# schematic.net
KiCad netlist of a schematic drawn in EasyEDA
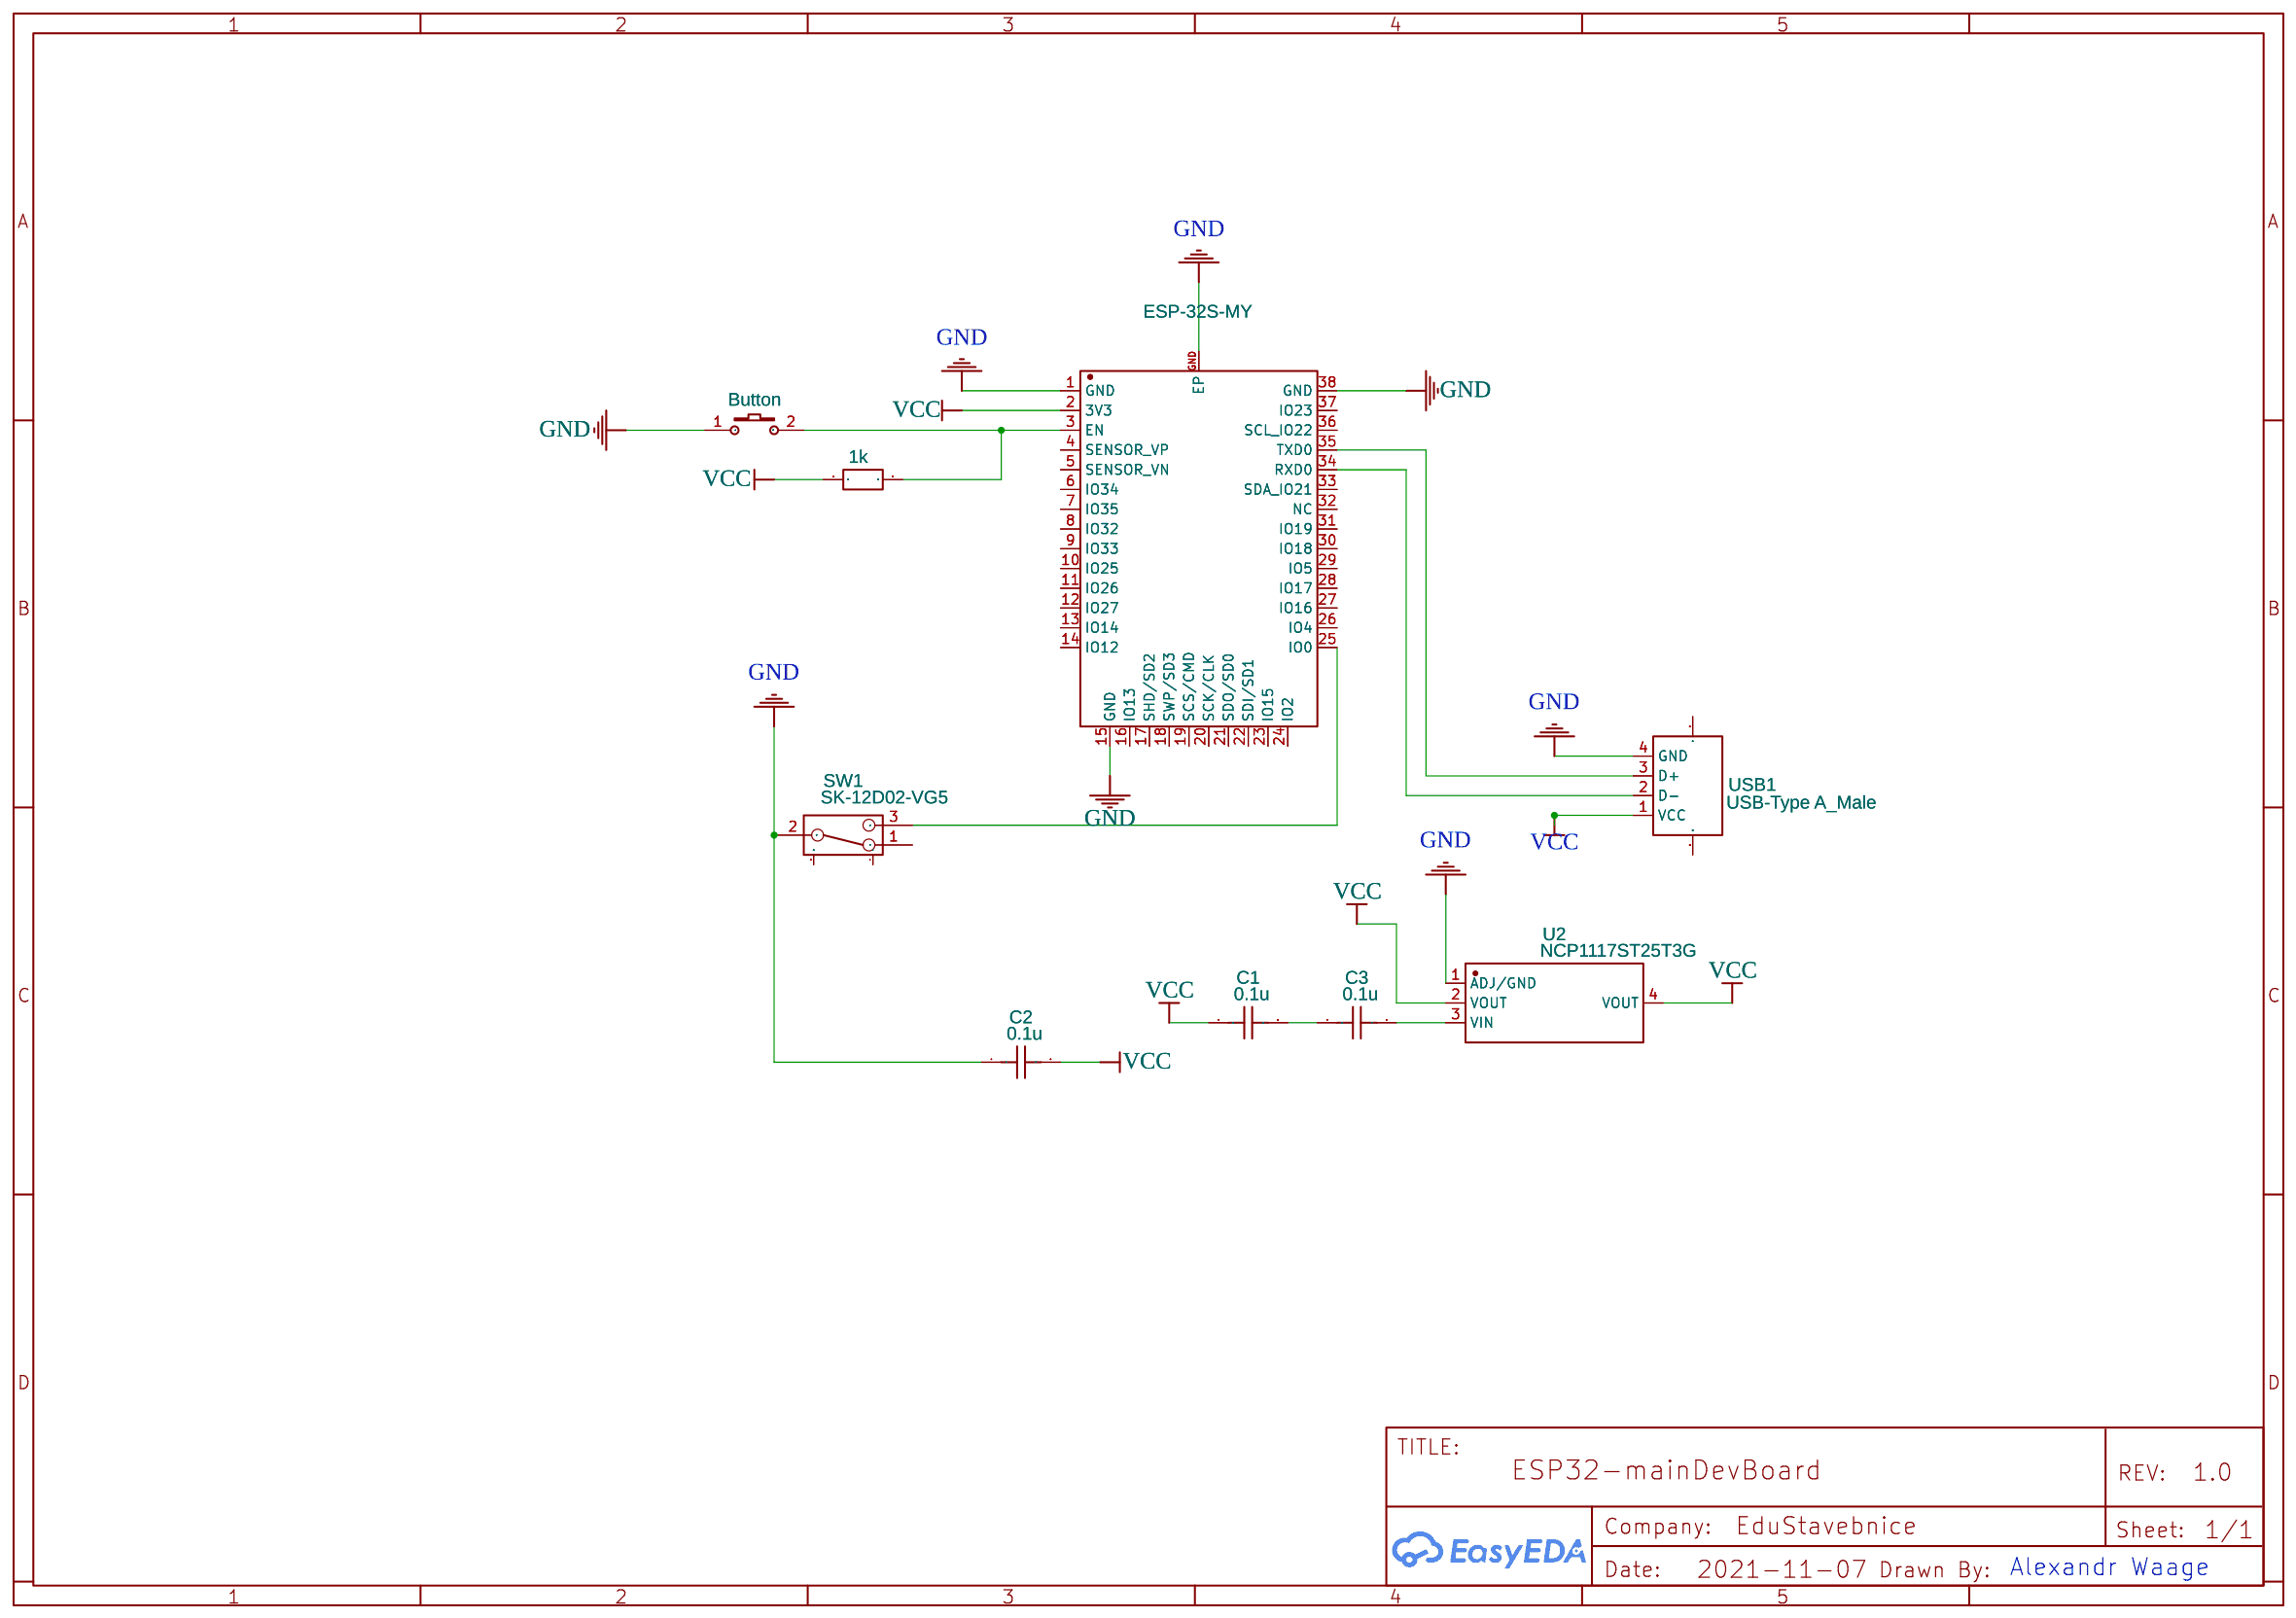
[diagram p0: schematic sheet]

(export (version "E")
  (design (tool "Eeschema 10.0.6"))
  (components
    (comp (ref "C1") (value "0.1u") (libsource (lib "") (part "C_0603_US")))
    (comp (ref "C2") (value "0.1u") (libsource (lib "") (part "C_0603_US")))
    (comp (ref "C3") (value "0.1u") (libsource (lib "") (part "C_0603_US")))
    (comp (ref "KEY1")
      (value "Button")
      (fields
        (field (name "BOM_Manufacturer Part") "K2-1107ST-A4SW-06")
        (field (name "BOM_Supplier Part") "C118141")
      )
      (libsource (lib "") (part "K2-3.6×6.1_SMD"))
    )
    (comp (ref "R1") (value "1k") (libsource (lib "") (part "R_0603_EU")))
    (comp (ref "SW1")
      (value "SK-12D02-VG5")
      (fields (field (name "BOM_Supplier Part") "C136722"))
      (libsource (lib "") (part "SK-12D02-VG5"))
    )
    (comp (ref "U1") (value "ESP-32S-MY") (libsource (lib "") (part "ESP-32S-MY")))
    (comp (ref "U2")
      (value "NCP1117ST25T3G")
      (fields (field (name "BOM_Supplier Part") "C233237"))
      (libsource (lib "") (part "NCP1117ST25T3G"))
    )
    (comp (ref "USB1")
      (value "USB-Type A_Male")
      (fields (field (name "BOM_Manufacturer Part") "USB-05") (field (name "BOM_Supplier Part") "C112454"))
      (libsource (lib "") (part "USB-Type A_Male"))
    )
  )
  (nets
    (net (code "1") (name "GND") (class "Default")
      (node (ref "C2") (pin "1") (pinfunction "1_1") (pintype "unspecified"))
      (node (ref "KEY1") (pin "1") (pinfunction "1_1") (pintype "unspecified"))
      (node (ref "SW1") (pin "2") (pinfunction "2_2") (pintype "unspecified"))
      (node (ref "U1") (pin "1") (pinfunction "GND_1") (pintype "unspecified"))
      (node (ref "U1") (pin "15") (pinfunction "GND_15") (pintype "unspecified"))
      (node (ref "U1") (pin "38") (pinfunction "GND_38") (pintype "unspecified"))
      (node (ref "U1") (pin "GND") (pinfunction "EP_GND") (pintype "unspecified"))
      (node (ref "U2") (pin "1") (pinfunction "ADJ/GND_1") (pintype "unspecified"))
      (node (ref "USB1") (pin "4") (pinfunction "GND_4") (pintype "input"))
    )
    (net (code "2") (name "Net-(C1-Pad2)") (class "Default")
      (node (ref "C1") (pin "2") (pinfunction "2_2") (pintype "unspecified"))
      (node (ref "C3") (pin "1") (pinfunction "1_1") (pintype "unspecified"))
    )
    (net (code "3") (name "Net-(U1-EN)") (class "Default")
      (node (ref "KEY1") (pin "2") (pinfunction "2_2") (pintype "unspecified"))
      (node (ref "R1") (pin "2") (pinfunction "2_2") (pintype "unspecified"))
      (node (ref "U1") (pin "3") (pinfunction "EN_3") (pintype "unspecified"))
    )
    (net (code "4") (name "Net-(U1-IO0)") (class "Default")
      (node (ref "SW1") (pin "3") (pinfunction "3_3") (pintype "unspecified"))
      (node (ref "U1") (pin "25") (pinfunction "IO0_25") (pintype "unspecified"))
    )
    (net (code "5") (name "Net-(U1-RXD0)") (class "Default")
      (node (ref "U1") (pin "34") (pinfunction "RXD0_34") (pintype "unspecified"))
      (node (ref "USB1") (pin "2") (pinfunction "D-_2") (pintype "input"))
    )
    (net (code "6") (name "Net-(U1-TXD0)") (class "Default")
      (node (ref "U1") (pin "35") (pinfunction "TXD0_35") (pintype "unspecified"))
      (node (ref "USB1") (pin "3") (pinfunction "D+_3") (pintype "input"))
    )
    (net (code "7") (name "Net-(U2-VIN)") (class "Default")
      (node (ref "C3") (pin "2") (pinfunction "2_2") (pintype "unspecified"))
      (node (ref "U2") (pin "3") (pinfunction "VIN_3") (pintype "unspecified"))
    )
    (net (code "8") (name "VCC") (class "Default")
      (node (ref "C1") (pin "1") (pinfunction "1_1") (pintype "unspecified"))
      (node (ref "C2") (pin "2") (pinfunction "2_2") (pintype "unspecified"))
      (node (ref "R1") (pin "1") (pinfunction "1_1") (pintype "unspecified"))
      (node (ref "U1") (pin "2") (pinfunction "3V3_2") (pintype "unspecified"))
      (node (ref "U2") (pin "2") (pinfunction "VOUT_2") (pintype "unspecified"))
      (node (ref "U2") (pin "4") (pinfunction "VOUT_4") (pintype "unspecified"))
      (node (ref "USB1") (pin "1") (pinfunction "VCC_1") (pintype "input"))
    )
    (net (code "9") (name "unconnected-(SW1-Pad1)") (class "Default")
      (node (ref "SW1") (pin "1") (pinfunction "1_1") (pintype "unspecified"))
    )
    (net (code "10") (name "unconnected-(SW1-Pad4)") (class "Default")
      (node (ref "SW1") (pin "4") (pinfunction "4_4") (pintype "unspecified"))
    )
    (net (code "11") (name "unconnected-(SW1-Pad5)") (class "Default")
      (node (ref "SW1") (pin "5") (pinfunction "5_5") (pintype "unspecified"))
    )
    (net (code "12") (name "unconnected-(U1-IO2-Pad24)") (class "Default")
      (node (ref "U1") (pin "24") (pinfunction "IO2_24") (pintype "unspecified"))
    )
    (net (code "13") (name "unconnected-(U1-IO4-Pad26)") (class "Default")
      (node (ref "U1") (pin "26") (pinfunction "IO4_26") (pintype "unspecified"))
    )
    (net (code "14") (name "unconnected-(U1-IO5-Pad29)") (class "Default")
      (node (ref "U1") (pin "29") (pinfunction "IO5_29") (pintype "unspecified"))
    )
    (net (code "15") (name "unconnected-(U1-IO12-Pad14)") (class "Default")
      (node (ref "U1") (pin "14") (pinfunction "IO12_14") (pintype "unspecified"))
    )
    (net (code "16") (name "unconnected-(U1-IO13-Pad16)") (class "Default")
      (node (ref "U1") (pin "16") (pinfunction "IO13_16") (pintype "unspecified"))
    )
    (net (code "17") (name "unconnected-(U1-IO14-Pad13)") (class "Default")
      (node (ref "U1") (pin "13") (pinfunction "IO14_13") (pintype "unspecified"))
    )
    (net (code "18") (name "unconnected-(U1-IO15-Pad23)") (class "Default")
      (node (ref "U1") (pin "23") (pinfunction "IO15_23") (pintype "unspecified"))
    )
    (net (code "19") (name "unconnected-(U1-IO16-Pad27)") (class "Default")
      (node (ref "U1") (pin "27") (pinfunction "IO16_27") (pintype "unspecified"))
    )
    (net (code "20") (name "unconnected-(U1-IO17-Pad28)") (class "Default")
      (node (ref "U1") (pin "28") (pinfunction "IO17_28") (pintype "unspecified"))
    )
    (net (code "21") (name "unconnected-(U1-IO18-Pad30)") (class "Default")
      (node (ref "U1") (pin "30") (pinfunction "IO18_30") (pintype "unspecified"))
    )
    (net (code "22") (name "unconnected-(U1-IO19-Pad31)") (class "Default")
      (node (ref "U1") (pin "31") (pinfunction "IO19_31") (pintype "unspecified"))
    )
    (net (code "23") (name "unconnected-(U1-IO23-Pad37)") (class "Default")
      (node (ref "U1") (pin "37") (pinfunction "IO23_37") (pintype "unspecified"))
    )
    (net (code "24") (name "unconnected-(U1-IO25-Pad10)") (class "Default")
      (node (ref "U1") (pin "10") (pinfunction "IO25_10") (pintype "unspecified"))
    )
    (net (code "25") (name "unconnected-(U1-IO26-Pad11)") (class "Default")
      (node (ref "U1") (pin "11") (pinfunction "IO26_11") (pintype "unspecified"))
    )
    (net (code "26") (name "unconnected-(U1-IO27-Pad12)") (class "Default")
      (node (ref "U1") (pin "12") (pinfunction "IO27_12") (pintype "unspecified"))
    )
    (net (code "27") (name "unconnected-(U1-IO32-Pad8)") (class "Default")
      (node (ref "U1") (pin "8") (pinfunction "IO32_8") (pintype "unspecified"))
    )
    (net (code "28") (name "unconnected-(U1-IO33-Pad9)") (class "Default")
      (node (ref "U1") (pin "9") (pinfunction "IO33_9") (pintype "unspecified"))
    )
    (net (code "29") (name "unconnected-(U1-IO34-Pad6)") (class "Default")
      (node (ref "U1") (pin "6") (pinfunction "IO34_6") (pintype "unspecified"))
    )
    (net (code "30") (name "unconnected-(U1-IO35-Pad7)") (class "Default")
      (node (ref "U1") (pin "7") (pinfunction "IO35_7") (pintype "unspecified"))
    )
    (net (code "31") (name "unconnected-(U1-NC-Pad32)") (class "Default")
      (node (ref "U1") (pin "32") (pinfunction "NC_32") (pintype "unspecified"))
    )
    (net (code "32") (name "unconnected-(U1-SCK{slash}CLK-Pad20)") (class "Default")
      (node (ref "U1") (pin "20") (pinfunction "SCK/CLK_20") (pintype "unspecified"))
    )
    (net (code "33") (name "unconnected-(U1-SCL_IO22-Pad36)") (class "Default")
      (node (ref "U1") (pin "36") (pinfunction "SCL_IO22_36") (pintype "unspecified"))
    )
    (net (code "34") (name "unconnected-(U1-SCS{slash}CMD-Pad19)") (class "Default")
      (node (ref "U1") (pin "19") (pinfunction "SCS/CMD_19") (pintype "unspecified"))
    )
    (net (code "35") (name "unconnected-(U1-SDA_IO21-Pad33)") (class "Default")
      (node (ref "U1") (pin "33") (pinfunction "SDA_IO21_33") (pintype "unspecified"))
    )
    (net (code "36") (name "unconnected-(U1-SDI{slash}SD1-Pad22)") (class "Default")
      (node (ref "U1") (pin "22") (pinfunction "SDI/SD1_22") (pintype "unspecified"))
    )
    (net (code "37") (name "unconnected-(U1-SDO{slash}SD0-Pad21)") (class "Default")
      (node (ref "U1") (pin "21") (pinfunction "SDO/SD0_21") (pintype "unspecified"))
    )
    (net (code "38") (name "unconnected-(U1-SENSOR_VN-Pad5)") (class "Default")
      (node (ref "U1") (pin "5") (pinfunction "SENSOR_VN_5") (pintype "unspecified"))
    )
    (net (code "39") (name "unconnected-(U1-SENSOR_VP-Pad4)") (class "Default")
      (node (ref "U1") (pin "4") (pinfunction "SENSOR_VP_4") (pintype "unspecified"))
    )
    (net (code "40") (name "unconnected-(U1-SHD{slash}SD2-Pad17)") (class "Default")
      (node (ref "U1") (pin "17") (pinfunction "SHD/SD2_17") (pintype "unspecified"))
    )
    (net (code "41") (name "unconnected-(U1-SWP{slash}SD3-Pad18)") (class "Default")
      (node (ref "U1") (pin "18") (pinfunction "SWP/SD3_18") (pintype "unspecified"))
    )
    (net (code "42") (name "unconnected-(USB1-Pad5)") (class "Default")
      (node (ref "USB1") (pin "5") (pinfunction "5_5") (pintype "unspecified"))
    )
    (net (code "43") (name "unconnected-(USB1-Pad6)") (class "Default")
      (node (ref "USB1") (pin "6") (pinfunction "6_6") (pintype "unspecified"))
    )
  )
)
